# DASH_V_3_LEDS_POWER.net
KiCad netlist of a schematic drawn in Altium Designer
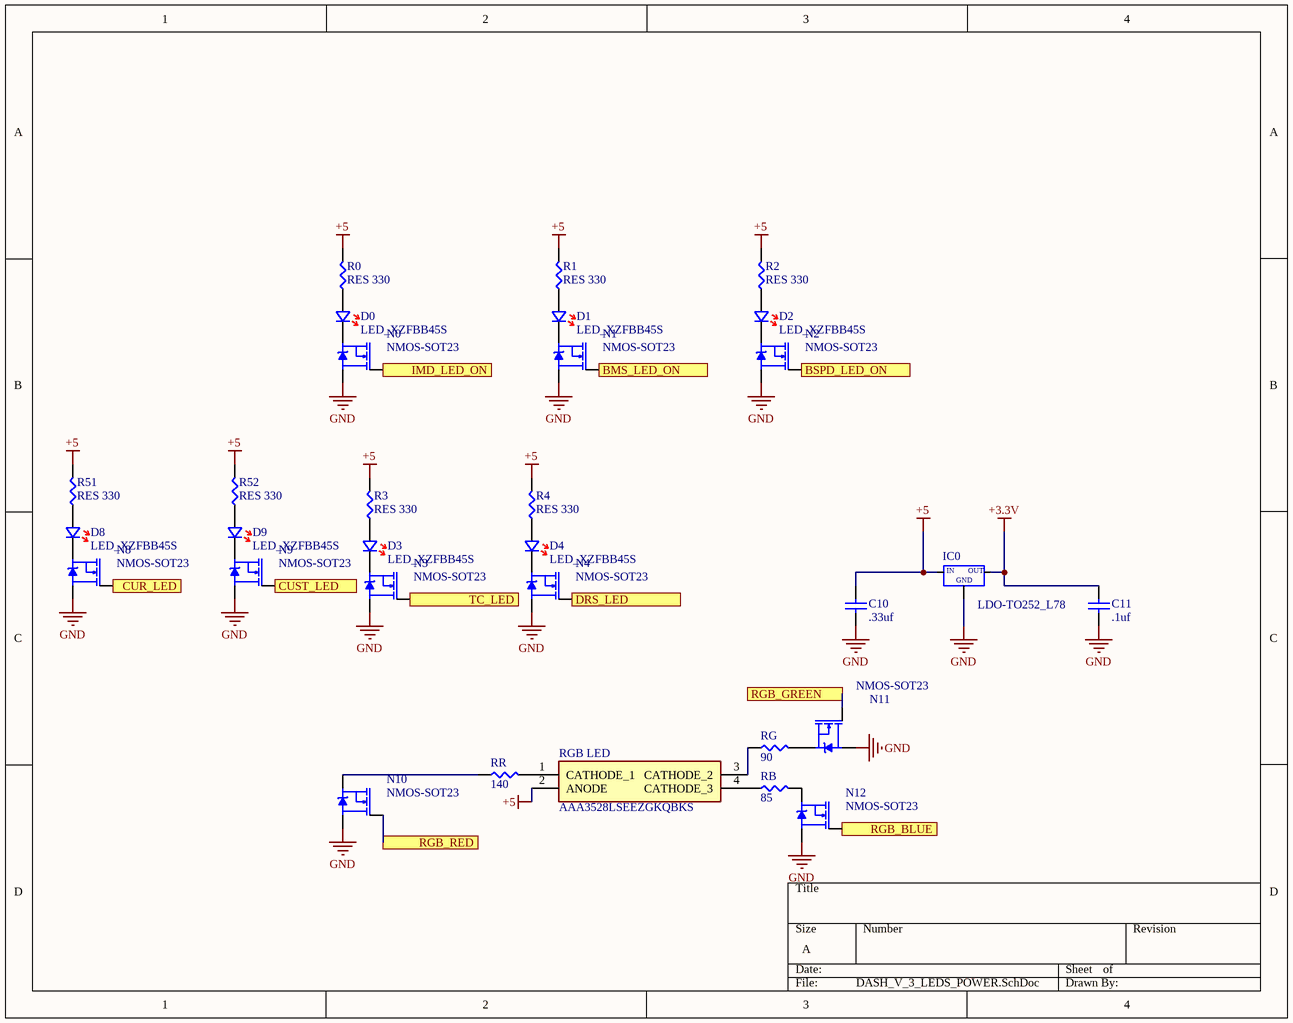
[diagram p0: DASH_V_3_LEDS_POWER.SchDoc]

(export (version "E")
  (design (tool "Eeschema 10.0.6"))
  (components
    (comp (ref "C10")
      (value ".33uf")
      (footprint "CAPC1608X87X35NL15T15")
      (description ".1 uf")
      (fields (field (name "PART NUMBER") "C0603C104J3RAC7867") (field (name "MANUFACTURER") "Kemet"))
      (libsource (lib "Altium Content Vault") (part "CAP"))
    )
    (comp (ref "C11")
      (value ".1uf")
      (footprint "CAPC1608X87X35NL15T15")
      (description ".1 uf")
      (fields (field (name "PART NUMBER") "C0603C104J3RAC7867") (field (name "MANUFACTURER") "Kemet"))
      (libsource (lib "Altium Content Vault") (part "CAP"))
    )
    (comp (ref "D0")
      (value "LED_XZFBB45S")
      (footprint "LED_XZFBB45S")
      (libsource (lib "ife19_Elec_Library") (part "LED_XZFBB45S"))
    )
    (comp (ref "D1")
      (value "LED_XZFBB45S")
      (footprint "LED_XZFBB45S")
      (libsource (lib "ife19_Elec_Library") (part "LED_XZFBB45S"))
    )
    (comp (ref "D2")
      (value "LED_XZFBB45S")
      (footprint "LED_XZFBB45S")
      (libsource (lib "ife19_Elec_Library") (part "LED_XZFBB45S"))
    )
    (comp (ref "D3")
      (value "LED_XZFBB45S")
      (footprint "LED_XZFBB45S")
      (libsource (lib "ife19_Elec_Library") (part "LED_XZFBB45S"))
    )
    (comp (ref "D4")
      (value "LED_XZFBB45S")
      (footprint "LED_XZFBB45S")
      (libsource (lib "ife19_Elec_Library") (part "LED_XZFBB45S"))
    )
    (comp (ref "D8")
      (value "LED_XZFBB45S")
      (footprint "LED_XZFBB45S")
      (libsource (lib "ife19_Elec_Library") (part "LED_XZFBB45S"))
    )
    (comp (ref "D9")
      (value "LED_XZFBB45S")
      (footprint "LED_XZFBB45S")
      (libsource (lib "ife19_Elec_Library") (part "LED_XZFBB45S"))
    )
    (comp (ref "IC0")
      (value "LDO-TO252_L78")
      (footprint "TO252")
      (libsource (lib "ife19_Elec_Library") (part "LDO-TO252_L78"))
    )
    (comp (ref "N0")
      (value "NMOS-SOT23")
      (footprint "SOT23")
      (libsource (lib "ife19_Elec_Library") (part "NMOS-SOT23"))
    )
    (comp (ref "N1")
      (value "NMOS-SOT23")
      (footprint "SOT23")
      (libsource (lib "ife19_Elec_Library") (part "NMOS-SOT23"))
    )
    (comp (ref "N2")
      (value "NMOS-SOT23")
      (footprint "SOT23")
      (libsource (lib "ife19_Elec_Library") (part "NMOS-SOT23"))
    )
    (comp (ref "N3")
      (value "NMOS-SOT23")
      (footprint "SOT23")
      (libsource (lib "ife19_Elec_Library") (part "NMOS-SOT23"))
    )
    (comp (ref "N4")
      (value "NMOS-SOT23")
      (footprint "SOT23")
      (libsource (lib "ife19_Elec_Library") (part "NMOS-SOT23"))
    )
    (comp (ref "N8")
      (value "NMOS-SOT23")
      (footprint "SOT23")
      (libsource (lib "ife19_Elec_Library") (part "NMOS-SOT23"))
    )
    (comp (ref "N9")
      (value "NMOS-SOT23")
      (footprint "SOT23")
      (libsource (lib "ife19_Elec_Library") (part "NMOS-SOT23"))
    )
    (comp (ref "N10")
      (value "NMOS-SOT23")
      (footprint "SOT23")
      (libsource (lib "ife19_Elec_Library") (part "NMOS-SOT23"))
    )
    (comp (ref "N11")
      (value "NMOS-SOT23")
      (footprint "SOT23")
      (libsource (lib "ife19_Elec_Library") (part "NMOS-SOT23"))
    )
    (comp (ref "N12")
      (value "NMOS-SOT23")
      (footprint "SOT23")
      (libsource (lib "ife19_Elec_Library") (part "NMOS-SOT23"))
    )
    (comp (ref "R0")
      (value "RES 330")
      (footprint "RES-0603")
      (libsource (lib "ife19_Elec_Library") (part "RES-0603"))
    )
    (comp (ref "R1")
      (value "RES 330")
      (footprint "RES-0603")
      (libsource (lib "ife19_Elec_Library") (part "RES-0603"))
    )
    (comp (ref "R2")
      (value "RES 330")
      (footprint "RES-0603")
      (libsource (lib "ife19_Elec_Library") (part "RES-0603"))
    )
    (comp (ref "R3")
      (value "RES 330")
      (footprint "RES-0603")
      (libsource (lib "ife19_Elec_Library") (part "RES-0603"))
    )
    (comp (ref "R4")
      (value "RES 330")
      (footprint "RES-0603")
      (libsource (lib "ife19_Elec_Library") (part "RES-0603"))
    )
    (comp (ref "R51")
      (value "RES 330")
      (footprint "RES-0603")
      (libsource (lib "ife19_Elec_Library") (part "RES-0603"))
    )
    (comp (ref "R52")
      (value "RES 330")
      (footprint "RES-0603")
      (libsource (lib "ife19_Elec_Library") (part "RES-0603"))
    )
    (comp (ref "RB")
      (value "85")
      (footprint "RES-0603")
      (libsource (lib "ife19_Elec_Library") (part "RES-0603"))
    )
    (comp (ref "RG")
      (value "90")
      (footprint "RES-0603")
      (libsource (lib "ife19_Elec_Library") (part "RES-0603"))
    )
    (comp (ref "RGB LED")
      (value "AAA3528LSEEZGKQBKS")
      (footprint "SamacSys:AAA3528")
      (description "LED")
      (fields (field (name "MOUSER PART NUMBER") "604-AAA3528LSEEZGKQB"))
      (libsource (lib "*") (part "AAA3528LSEEZGKQBKS"))
    )
    (comp (ref "RR")
      (value "140")
      (footprint "RES-0603")
      (libsource (lib "ife19_Elec_Library") (part "RES-0603"))
    )
  )
  (nets
    (net (code "1") (name "+3.3V") (class "Default")
      (node (ref "C11") (pin "2") (pinfunction "2_2") (pintype "passive"))
      (node (ref "IC0") (pin "3") (pinfunction "22_3") (pintype "passive"))
    )
    (net (code "2") (name "+5") (class "Default")
      (node (ref "C10") (pin "2") (pinfunction "2_2") (pintype "passive"))
      (node (ref "IC0") (pin "1") (pinfunction "21_1") (pintype "passive"))
      (node (ref "R0") (pin "2") (pinfunction "2_2") (pintype "passive"))
      (node (ref "R1") (pin "2") (pinfunction "2_2") (pintype "passive"))
      (node (ref "R2") (pin "2") (pinfunction "2_2") (pintype "passive"))
      (node (ref "R3") (pin "2") (pinfunction "2_2") (pintype "passive"))
      (node (ref "R4") (pin "2") (pinfunction "2_2") (pintype "passive"))
      (node (ref "R51") (pin "2") (pinfunction "2_2") (pintype "passive"))
      (node (ref "R52") (pin "2") (pinfunction "2_2") (pintype "passive"))
      (node (ref "RGB LED") (pin "2") (pinfunction "ANODE_2") (pintype "passive"))
    )
    (net (code "3") (name "/BMS_LED_ON") (class "Default")
      (node (ref "N1") (pin "1") (pinfunction "G_1") (pintype "passive"))
    )
    (net (code "4") (name "/BSPD_LED_ON") (class "Default")
      (node (ref "N2") (pin "1") (pinfunction "G_1") (pintype "passive"))
    )
    (net (code "5") (name "/CUR_LED") (class "Default")
      (node (ref "N8") (pin "1") (pinfunction "G_1") (pintype "passive"))
    )
    (net (code "6") (name "/CUST_LED") (class "Default")
      (node (ref "N9") (pin "1") (pinfunction "G_1") (pintype "passive"))
    )
    (net (code "7") (name "/DRS_LED") (class "Default")
      (node (ref "N4") (pin "1") (pinfunction "G_1") (pintype "passive"))
    )
    (net (code "8") (name "/IMD_LED_ON") (class "Default")
      (node (ref "N0") (pin "1") (pinfunction "G_1") (pintype "passive"))
    )
    (net (code "9") (name "/RGB_BLUE") (class "Default")
      (node (ref "N12") (pin "1") (pinfunction "G_1") (pintype "passive"))
    )
    (net (code "10") (name "/RGB_GREEN") (class "Default")
      (node (ref "N11") (pin "1") (pinfunction "G_1") (pintype "passive"))
    )
    (net (code "11") (name "/RGB_RED") (class "Default")
      (node (ref "N10") (pin "1") (pinfunction "G_1") (pintype "passive"))
    )
    (net (code "12") (name "/TC_LED") (class "Default")
      (node (ref "N3") (pin "1") (pinfunction "G_1") (pintype "passive"))
    )
    (net (code "13") (name "GND") (class "Default")
      (node (ref "C10") (pin "1") (pinfunction "1_1") (pintype "passive"))
      (node (ref "C11") (pin "1") (pinfunction "1_1") (pintype "passive"))
      (node (ref "IC0") (pin "2") (pinfunction "23_2") (pintype "passive"))
      (node (ref "N0") (pin "2") (pinfunction "S_2") (pintype "passive"))
      (node (ref "N1") (pin "2") (pinfunction "S_2") (pintype "passive"))
      (node (ref "N10") (pin "2") (pinfunction "S_2") (pintype "passive"))
      (node (ref "N11") (pin "2") (pinfunction "S_2") (pintype "passive"))
      (node (ref "N12") (pin "2") (pinfunction "S_2") (pintype "passive"))
      (node (ref "N2") (pin "2") (pinfunction "S_2") (pintype "passive"))
      (node (ref "N3") (pin "2") (pinfunction "S_2") (pintype "passive"))
      (node (ref "N4") (pin "2") (pinfunction "S_2") (pintype "passive"))
      (node (ref "N8") (pin "2") (pinfunction "S_2") (pintype "passive"))
      (node (ref "N9") (pin "2") (pinfunction "S_2") (pintype "passive"))
    )
    (net (code "14") (name "Net-(D0-PadA)") (class "Default")
      (node (ref "D0") (pin "A") (pinfunction "A_A") (pintype "passive"))
      (node (ref "R0") (pin "1") (pinfunction "1_1") (pintype "passive"))
    )
    (net (code "15") (name "Net-(D1-PadA)") (class "Default")
      (node (ref "D1") (pin "A") (pinfunction "A_A") (pintype "passive"))
      (node (ref "R1") (pin "1") (pinfunction "1_1") (pintype "passive"))
    )
    (net (code "16") (name "Net-(D2-PadA)") (class "Default")
      (node (ref "D2") (pin "A") (pinfunction "A_A") (pintype "passive"))
      (node (ref "R2") (pin "1") (pinfunction "1_1") (pintype "passive"))
    )
    (net (code "17") (name "Net-(D3-PadA)") (class "Default")
      (node (ref "D3") (pin "A") (pinfunction "A_A") (pintype "passive"))
      (node (ref "R3") (pin "1") (pinfunction "1_1") (pintype "passive"))
    )
    (net (code "18") (name "Net-(D4-PadA)") (class "Default")
      (node (ref "D4") (pin "A") (pinfunction "A_A") (pintype "passive"))
      (node (ref "R4") (pin "1") (pinfunction "1_1") (pintype "passive"))
    )
    (net (code "19") (name "Net-(D8-PadA)") (class "Default")
      (node (ref "D8") (pin "A") (pinfunction "A_A") (pintype "passive"))
      (node (ref "R51") (pin "1") (pinfunction "1_1") (pintype "passive"))
    )
    (net (code "20") (name "Net-(D9-PadA)") (class "Default")
      (node (ref "D9") (pin "A") (pinfunction "A_A") (pintype "passive"))
      (node (ref "R52") (pin "1") (pinfunction "1_1") (pintype "passive"))
    )
    (net (code "21") (name "Net-(N0-D)") (class "Default")
      (node (ref "D0") (pin "K") (pinfunction "K_K") (pintype "passive"))
      (node (ref "N0") (pin "3") (pinfunction "D_3") (pintype "passive"))
    )
    (net (code "22") (name "Net-(N1-D)") (class "Default")
      (node (ref "D1") (pin "K") (pinfunction "K_K") (pintype "passive"))
      (node (ref "N1") (pin "3") (pinfunction "D_3") (pintype "passive"))
    )
    (net (code "23") (name "Net-(N2-D)") (class "Default")
      (node (ref "D2") (pin "K") (pinfunction "K_K") (pintype "passive"))
      (node (ref "N2") (pin "3") (pinfunction "D_3") (pintype "passive"))
    )
    (net (code "24") (name "Net-(N3-D)") (class "Default")
      (node (ref "D3") (pin "K") (pinfunction "K_K") (pintype "passive"))
      (node (ref "N3") (pin "3") (pinfunction "D_3") (pintype "passive"))
    )
    (net (code "25") (name "Net-(N4-D)") (class "Default")
      (node (ref "D4") (pin "K") (pinfunction "K_K") (pintype "passive"))
      (node (ref "N4") (pin "3") (pinfunction "D_3") (pintype "passive"))
    )
    (net (code "26") (name "Net-(N8-D)") (class "Default")
      (node (ref "D8") (pin "K") (pinfunction "K_K") (pintype "passive"))
      (node (ref "N8") (pin "3") (pinfunction "D_3") (pintype "passive"))
    )
    (net (code "27") (name "Net-(N9-D)") (class "Default")
      (node (ref "D9") (pin "K") (pinfunction "K_K") (pintype "passive"))
      (node (ref "N9") (pin "3") (pinfunction "D_3") (pintype "passive"))
    )
    (net (code "28") (name "Net-(N10-D)") (class "Default")
      (node (ref "N10") (pin "3") (pinfunction "D_3") (pintype "passive"))
      (node (ref "RR") (pin "1") (pinfunction "1_1") (pintype "passive"))
    )
    (net (code "29") (name "Net-(N11-D)") (class "Default")
      (node (ref "N11") (pin "3") (pinfunction "D_3") (pintype "passive"))
      (node (ref "RG") (pin "2") (pinfunction "2_2") (pintype "passive"))
    )
    (net (code "30") (name "Net-(N12-D)") (class "Default")
      (node (ref "N12") (pin "3") (pinfunction "D_3") (pintype "passive"))
      (node (ref "RB") (pin "2") (pinfunction "2_2") (pintype "passive"))
    )
    (net (code "31") (name "Net-(RGB LED-CATHODE_1)") (class "Default")
      (node (ref "RGB LED") (pin "1") (pinfunction "CATHODE_1_1") (pintype "passive"))
      (node (ref "RR") (pin "2") (pinfunction "2_2") (pintype "passive"))
    )
    (net (code "32") (name "Net-(RGB LED-CATHODE_2)") (class "Default")
      (node (ref "RG") (pin "1") (pinfunction "1_1") (pintype "passive"))
      (node (ref "RGB LED") (pin "3") (pinfunction "CATHODE_2_3") (pintype "passive"))
    )
    (net (code "33") (name "Net-(RGB LED-CATHODE_3)") (class "Default")
      (node (ref "RB") (pin "1") (pinfunction "1_1") (pintype "passive"))
      (node (ref "RGB LED") (pin "4") (pinfunction "CATHODE_3_4") (pintype "passive"))
    )
  )
)
